# PhotoInterruptor.net
KiCad netlist of a schematic drawn in EAGLE
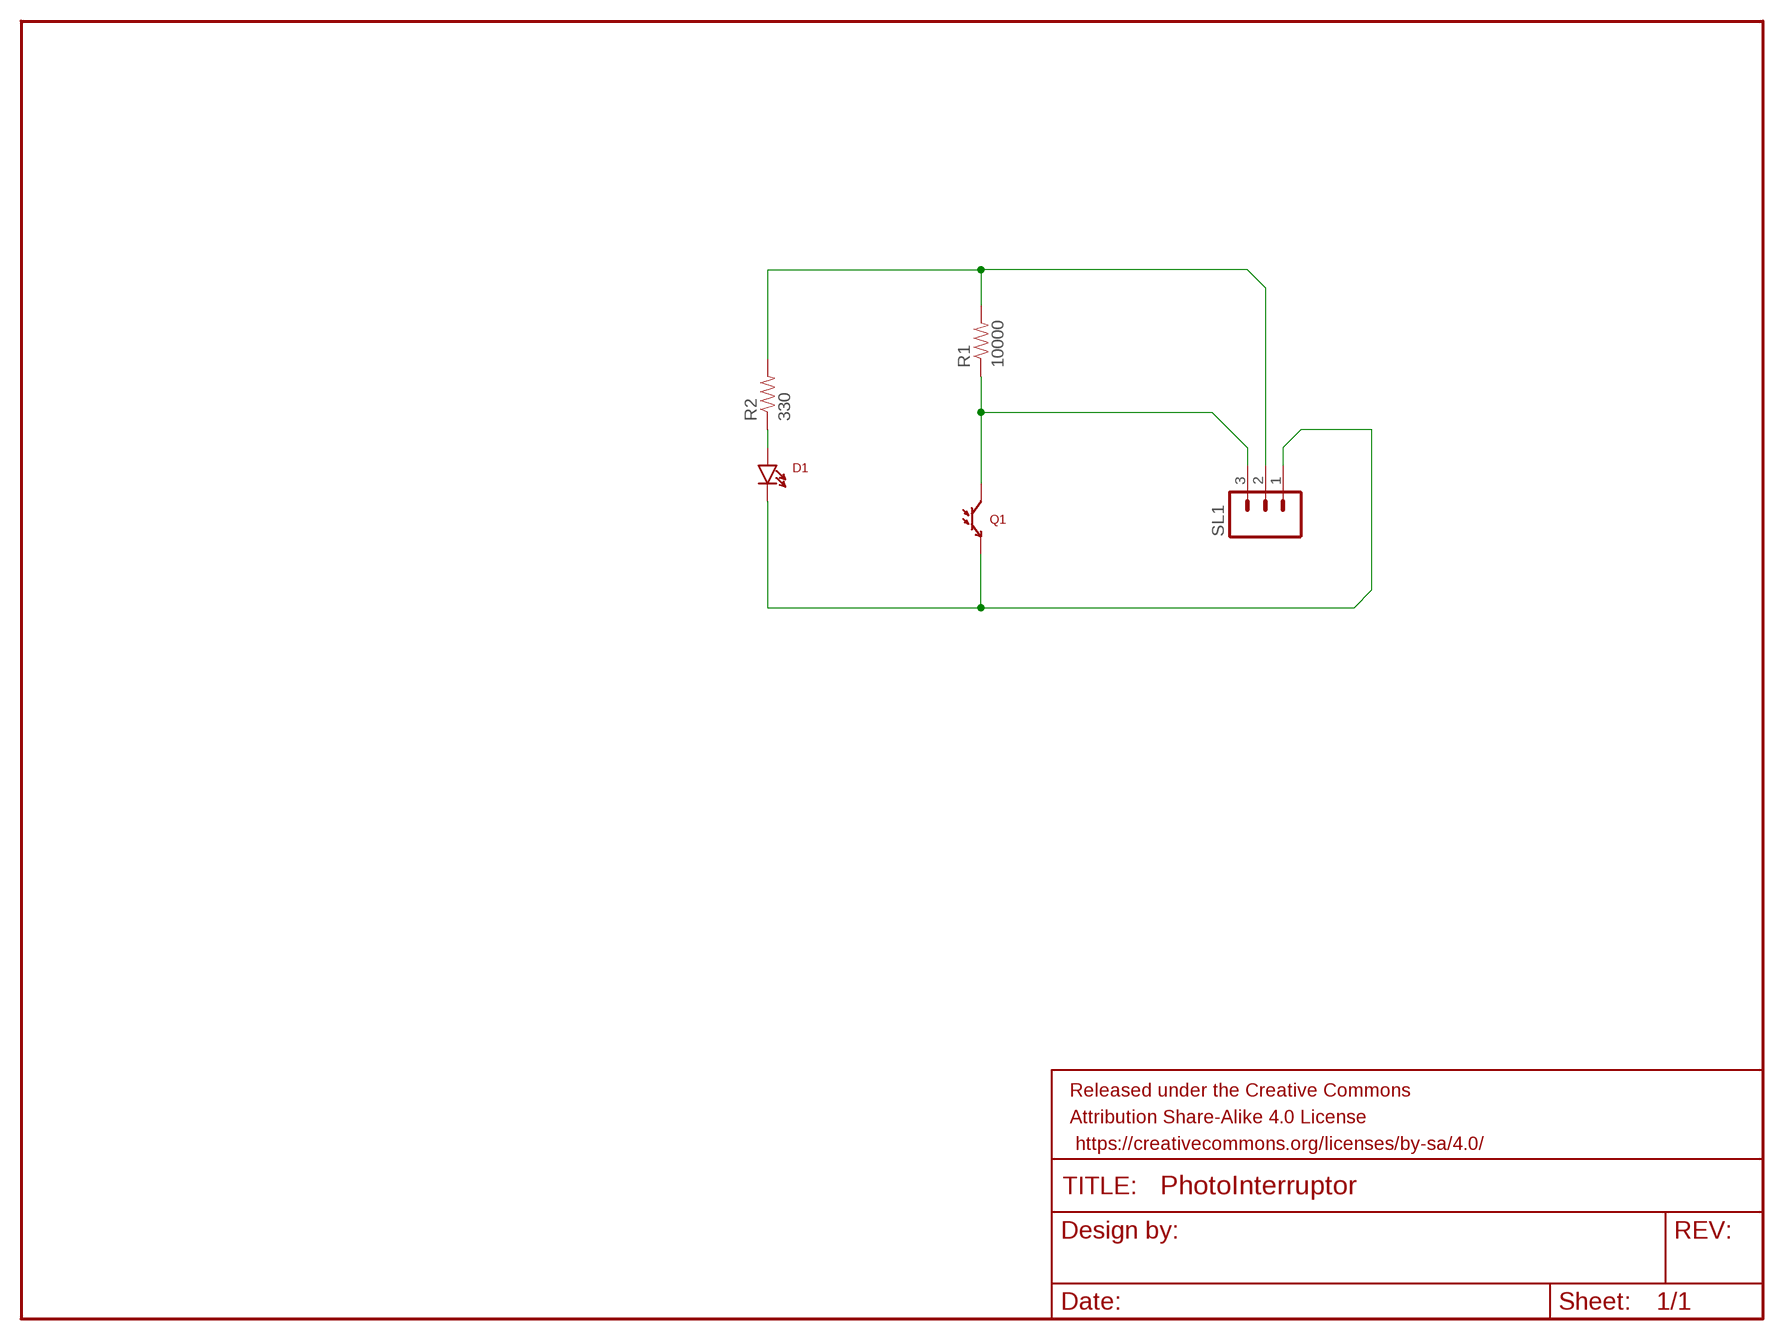
[diagram p0: schematic, sheet 1]

(export (version "E")
  (design (tool "Eeschema 10.0.6"))
  (components
    (comp (ref "D1")
      (value "LTE-302")
      (footprint "eagle-import:LTE-302")
      (libsource (lib "eagle-import") (part "LTE-302"))
    )
    (comp (ref "FRAME1")
      (value "FRAME-LETTERNO_PACKAGE")
      (footprint "eagle-import:DUMMY")
      (fields (field (name "DESIGNER") "Nobody"))
      (libsource (lib "eagle-import") (part "FRAME-LETTERNO_PACKAGE"))
    )
    (comp (ref "Q1")
      (value "LTR-301")
      (footprint "eagle-import:LTR-301")
      (libsource (lib "eagle-import") (part "LTR-301"))
    )
    (comp (ref "R1")
      (value "10000")
      (footprint "eagle-import:AXIAL-0.3")
      (libsource (lib "eagle-import") (part "10KOHM-1/4W-1%(PTH)HORIZ"))
    )
    (comp (ref "R2")
      (value "330")
      (footprint "eagle-import:AXIAL-0.3")
      (libsource (lib "eagle-import") (part "10KOHM-1/4W-1%(PTH)HORIZ"))
    )
    (comp (ref "SL1")
      (value "M03")
      (footprint "eagle-import:03P")
      (libsource (lib "eagle-import") (part "M03"))
    )
  )
  (nets
    (net (code "1") (name "Net-(D1-PadC)") (class "Default")
      (node (ref "D1") (pin "C") (pinfunction "C_C") (pintype "bidirectional"))
      (node (ref "Q1") (pin "E") (pinfunction "E_E") (pintype "bidirectional"))
      (node (ref "SL1") (pin "1") (pinfunction "1_1") (pintype "passive"))
    )
    (net (code "2") (name "Net-(R1-1)") (class "Default")
      (node (ref "Q1") (pin "C") (pinfunction "C_C") (pintype "bidirectional"))
      (node (ref "R1") (pin "P$1") (pinfunction "1_P$1") (pintype "passive"))
      (node (ref "SL1") (pin "3") (pinfunction "3_3") (pintype "passive"))
    )
    (net (code "3") (name "Net-(R1-2)") (class "Default")
      (node (ref "R1") (pin "P$2") (pinfunction "2_P$2") (pintype "passive"))
      (node (ref "R2") (pin "P$2") (pinfunction "2_P$2") (pintype "passive"))
      (node (ref "SL1") (pin "2") (pinfunction "2_2") (pintype "passive"))
    )
    (net (code "4") (name "Net-(R2-1)") (class "Default")
      (node (ref "D1") (pin "A") (pinfunction "A_A") (pintype "bidirectional"))
      (node (ref "R2") (pin "P$1") (pinfunction "1_P$1") (pintype "passive"))
    )
  )
)
